# Prototipo_2.net
KiCad netlist of a schematic drawn in EAGLE
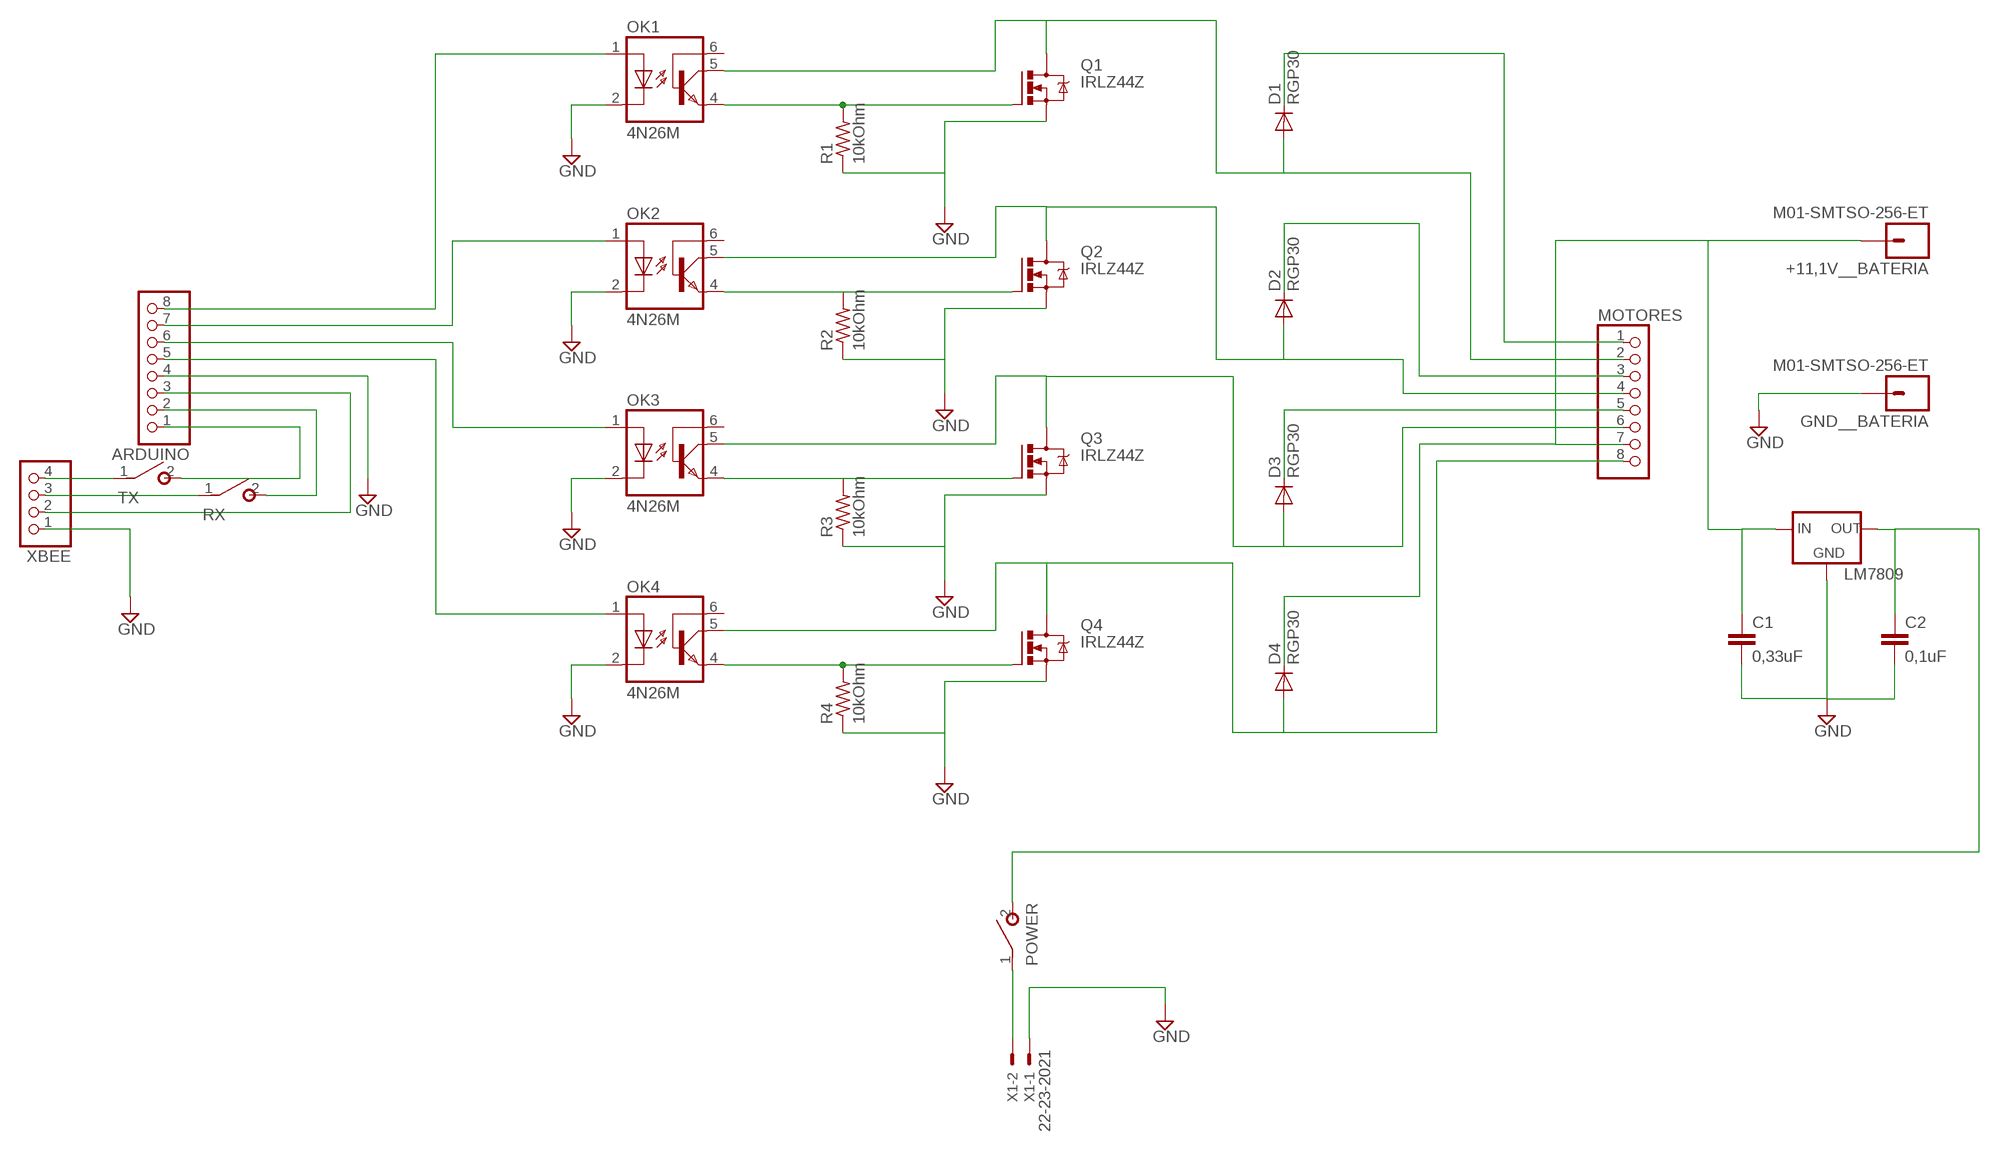
[diagram p0: schematic, sheet 1]

(export (version "E")
  (design (tool "Eeschema 10.0.6"))
  (components
    (comp (ref "+11,1V__BATERIA")
      (value "M01-SMTSO-256-ET")
      (footprint "eagle-import:SMTSO-256-ET")
      (libsource (lib "eagle-import") (part "M01-SMTSO-256-ET"))
    )
    (comp (ref "ARDUINO")
      (value "PINHD-1X8/90")
      (footprint "eagle-import:1X08_90")
      (libsource (lib "eagle-import") (part "PINHD-1X8/90"))
    )
    (comp (ref "C1")
      (value "0,33uF")
      (footprint "eagle-import:C050-030X075")
      (libsource (lib "eagle-import") (part "C-EU050-030X075"))
    )
    (comp (ref "C2")
      (value "0,1uF")
      (footprint "eagle-import:C050-030X075")
      (libsource (lib "eagle-import") (part "C-EU050-030X075"))
    )
    (comp (ref "D1")
      (value "RGP30")
      (footprint "eagle-import:DO201-15")
      (libsource (lib "eagle-import") (part "RGP30"))
    )
    (comp (ref "D2")
      (value "RGP30")
      (footprint "eagle-import:DO201-15")
      (libsource (lib "eagle-import") (part "RGP30"))
    )
    (comp (ref "D3")
      (value "RGP30")
      (footprint "eagle-import:DO201-15")
      (libsource (lib "eagle-import") (part "RGP30"))
    )
    (comp (ref "D4")
      (value "RGP30")
      (footprint "eagle-import:DO201-15")
      (libsource (lib "eagle-import") (part "RGP30"))
    )
    (comp (ref "GND__BATERIA")
      (value "M01-SMTSO-256-ET")
      (footprint "eagle-import:SMTSO-256-ET")
      (libsource (lib "eagle-import") (part "M01-SMTSO-256-ET"))
    )
    (comp (ref "LM7809")
      (value "78XXL")
      (footprint "eagle-import:78XXL")
      (libsource (lib "eagle-import") (part "78XXL"))
    )
    (comp (ref "MOTORES")
      (value "PINHD-1X8/90")
      (footprint "eagle-import:1X08_90")
      (libsource (lib "eagle-import") (part "PINHD-1X8/90"))
    )
    (comp (ref "OK1")
      (value "4N26M")
      (footprint "eagle-import:DIL06")
      (fields (field (name "MPN") "4N26-M"))
      (libsource (lib "eagle-import") (part "4N?M26"))
    )
    (comp (ref "OK2")
      (value "4N26M")
      (footprint "eagle-import:DIL06")
      (fields (field (name "MPN") "4N26-M"))
      (libsource (lib "eagle-import") (part "4N?M26"))
    )
    (comp (ref "OK3")
      (value "4N26M")
      (footprint "eagle-import:DIL06")
      (fields (field (name "MPN") "4N26-M"))
      (libsource (lib "eagle-import") (part "4N?M26"))
    )
    (comp (ref "OK4")
      (value "4N26M")
      (footprint "eagle-import:DIL06")
      (fields (field (name "MPN") "4N26-M"))
      (libsource (lib "eagle-import") (part "4N?M26"))
    )
    (comp (ref "POWER")
      (value "SPST")
      (footprint "eagle-import:SPST")
      (libsource (lib "eagle-import") (part "SPST"))
    )
    (comp (ref "Q1")
      (value "IRLZ44Z")
      (footprint "eagle-import:TO220BH")
      (libsource (lib "eagle-import") (part "IRLZ44Z"))
    )
    (comp (ref "Q2")
      (value "IRLZ44Z")
      (footprint "eagle-import:TO220BH")
      (libsource (lib "eagle-import") (part "IRLZ44Z"))
    )
    (comp (ref "Q3")
      (value "IRLZ44Z")
      (footprint "eagle-import:TO220BH")
      (libsource (lib "eagle-import") (part "IRLZ44Z"))
    )
    (comp (ref "Q4")
      (value "IRLZ44Z")
      (footprint "eagle-import:TO220BH")
      (libsource (lib "eagle-import") (part "IRLZ44Z"))
    )
    (comp (ref "R1")
      (value "10kOhm")
      (footprint "eagle-import:0207_7")
      (libsource (lib "eagle-import") (part "R-US_0207/7"))
    )
    (comp (ref "R2")
      (value "10kOhm")
      (footprint "eagle-import:0207_7")
      (libsource (lib "eagle-import") (part "R-US_0207/7"))
    )
    (comp (ref "R3")
      (value "10kOhm")
      (footprint "eagle-import:0207_7")
      (libsource (lib "eagle-import") (part "R-US_0207/7"))
    )
    (comp (ref "R4")
      (value "10kOhm")
      (footprint "eagle-import:0207_7")
      (libsource (lib "eagle-import") (part "R-US_0207/7"))
    )
    (comp (ref "RX")
      (value "SPST")
      (footprint "eagle-import:SPST")
      (libsource (lib "eagle-import") (part "SPST"))
    )
    (comp (ref "TX")
      (value "SPST")
      (footprint "eagle-import:SPST")
      (libsource (lib "eagle-import") (part "SPST"))
    )
    (comp (ref "X1")
      (value "22-23-2021")
      (footprint "eagle-import:22-23-2021")
      (fields (field (name "MF") "MOLEX"))
      (libsource (lib "eagle-import") (part "22-23-2021"))
    )
    (comp (ref "XBEE")
      (value "PINHD-1X4")
      (footprint "eagle-import:1X04")
      (libsource (lib "eagle-import") (part "PINHD-1X4"))
    )
  )
  (nets
    (net (code "1") (name "GND") (class "Default")
      (node (ref "ARDUINO") (pin "4") (pinfunction "4_4") (pintype "passive"))
      (node (ref "C1") (pin "2") (pinfunction "2_2") (pintype "passive"))
      (node (ref "C2") (pin "2") (pinfunction "2_2") (pintype "passive"))
      (node (ref "GND__BATERIA") (pin "P$1") (pinfunction "1_P$1") (pintype "passive"))
      (node (ref "LM7809") (pin "GND") (pinfunction "GND_GND") (pintype "input"))
      (node (ref "OK1") (pin "2") (pinfunction "C_2") (pintype "passive"))
      (node (ref "OK2") (pin "2") (pinfunction "C_2") (pintype "passive"))
      (node (ref "OK3") (pin "2") (pinfunction "C_2") (pintype "passive"))
      (node (ref "OK4") (pin "2") (pinfunction "C_2") (pintype "passive"))
      (node (ref "Q1") (pin "S") (pinfunction "S_S") (pintype "passive"))
      (node (ref "Q2") (pin "S") (pinfunction "S_S") (pintype "passive"))
      (node (ref "Q3") (pin "S") (pinfunction "S_S") (pintype "passive"))
      (node (ref "Q4") (pin "S") (pinfunction "S_S") (pintype "passive"))
      (node (ref "R1") (pin "1") (pinfunction "1_1") (pintype "passive"))
      (node (ref "R2") (pin "1") (pinfunction "1_1") (pintype "passive"))
      (node (ref "R3") (pin "1") (pinfunction "1_1") (pintype "passive"))
      (node (ref "R4") (pin "1") (pinfunction "1_1") (pintype "passive"))
      (node (ref "X1") (pin "1") (pinfunction "S_1") (pintype "passive"))
      (node (ref "XBEE") (pin "1") (pinfunction "1_1") (pintype "passive"))
    )
    (net (code "2") (name "Net-(+11,1V__BATERIA-1)") (class "Default")
      (node (ref "+11,1V__BATERIA") (pin "P$1") (pinfunction "1_P$1") (pintype "passive"))
      (node (ref "C1") (pin "1") (pinfunction "1_1") (pintype "passive"))
      (node (ref "D1") (pin "C") (pinfunction "C_C") (pintype "passive"))
      (node (ref "D2") (pin "C") (pinfunction "C_C") (pintype "passive"))
      (node (ref "D3") (pin "C") (pinfunction "C_C") (pintype "passive"))
      (node (ref "D4") (pin "C") (pinfunction "C_C") (pintype "passive"))
      (node (ref "LM7809") (pin "IN") (pinfunction "IN_IN") (pintype "input"))
      (node (ref "MOTORES") (pin "1") (pinfunction "1_1") (pintype "passive"))
      (node (ref "MOTORES") (pin "3") (pinfunction "3_3") (pintype "passive"))
      (node (ref "MOTORES") (pin "5") (pinfunction "5_5") (pintype "passive"))
      (node (ref "MOTORES") (pin "7") (pinfunction "7_7") (pintype "passive"))
    )
    (net (code "3") (name "Net-(ARDUINO-Pad3)") (class "Default")
      (node (ref "ARDUINO") (pin "3") (pinfunction "3_3") (pintype "passive"))
      (node (ref "XBEE") (pin "2") (pinfunction "2_2") (pintype "passive"))
    )
    (net (code "4") (name "Net-(OK1-A)") (class "Default")
      (node (ref "ARDUINO") (pin "8") (pinfunction "8_8") (pintype "passive"))
      (node (ref "OK1") (pin "1") (pinfunction "A_1") (pintype "passive"))
    )
    (net (code "5") (name "Net-(OK1-COL)") (class "Default")
      (node (ref "D1") (pin "A") (pinfunction "A_A") (pintype "passive"))
      (node (ref "MOTORES") (pin "2") (pinfunction "2_2") (pintype "passive"))
      (node (ref "OK1") (pin "5") (pinfunction "COL_5") (pintype "passive"))
      (node (ref "Q1") (pin "D") (pinfunction "D_D") (pintype "passive"))
    )
    (net (code "6") (name "Net-(OK1-EMI)") (class "Default")
      (node (ref "OK1") (pin "4") (pinfunction "EMI_4") (pintype "passive"))
      (node (ref "Q1") (pin "G") (pinfunction "G_G") (pintype "passive"))
      (node (ref "R1") (pin "2") (pinfunction "2_2") (pintype "passive"))
    )
    (net (code "7") (name "Net-(OK2-A)") (class "Default")
      (node (ref "ARDUINO") (pin "7") (pinfunction "7_7") (pintype "passive"))
      (node (ref "OK2") (pin "1") (pinfunction "A_1") (pintype "passive"))
    )
    (net (code "8") (name "Net-(OK2-COL)") (class "Default")
      (node (ref "D2") (pin "A") (pinfunction "A_A") (pintype "passive"))
      (node (ref "MOTORES") (pin "4") (pinfunction "4_4") (pintype "passive"))
      (node (ref "OK2") (pin "5") (pinfunction "COL_5") (pintype "passive"))
      (node (ref "Q2") (pin "D") (pinfunction "D_D") (pintype "passive"))
    )
    (net (code "9") (name "Net-(OK2-EMI)") (class "Default")
      (node (ref "OK2") (pin "4") (pinfunction "EMI_4") (pintype "passive"))
      (node (ref "Q2") (pin "G") (pinfunction "G_G") (pintype "passive"))
      (node (ref "R2") (pin "2") (pinfunction "2_2") (pintype "passive"))
    )
    (net (code "10") (name "Net-(OK3-A)") (class "Default")
      (node (ref "ARDUINO") (pin "6") (pinfunction "6_6") (pintype "passive"))
      (node (ref "OK3") (pin "1") (pinfunction "A_1") (pintype "passive"))
    )
    (net (code "11") (name "Net-(OK3-COL)") (class "Default")
      (node (ref "D3") (pin "A") (pinfunction "A_A") (pintype "passive"))
      (node (ref "MOTORES") (pin "6") (pinfunction "6_6") (pintype "passive"))
      (node (ref "OK3") (pin "5") (pinfunction "COL_5") (pintype "passive"))
      (node (ref "Q3") (pin "D") (pinfunction "D_D") (pintype "passive"))
    )
    (net (code "12") (name "Net-(OK3-EMI)") (class "Default")
      (node (ref "OK3") (pin "4") (pinfunction "EMI_4") (pintype "passive"))
      (node (ref "Q3") (pin "G") (pinfunction "G_G") (pintype "passive"))
      (node (ref "R3") (pin "2") (pinfunction "2_2") (pintype "passive"))
    )
    (net (code "13") (name "Net-(OK4-A)") (class "Default")
      (node (ref "ARDUINO") (pin "5") (pinfunction "5_5") (pintype "passive"))
      (node (ref "OK4") (pin "1") (pinfunction "A_1") (pintype "passive"))
    )
    (net (code "14") (name "Net-(OK4-COL)") (class "Default")
      (node (ref "D4") (pin "A") (pinfunction "A_A") (pintype "passive"))
      (node (ref "MOTORES") (pin "8") (pinfunction "8_8") (pintype "passive"))
      (node (ref "OK4") (pin "5") (pinfunction "COL_5") (pintype "passive"))
      (node (ref "Q4") (pin "D") (pinfunction "D_D") (pintype "passive"))
    )
    (net (code "15") (name "Net-(OK4-EMI)") (class "Default")
      (node (ref "OK4") (pin "4") (pinfunction "EMI_4") (pintype "passive"))
      (node (ref "Q4") (pin "G") (pinfunction "G_G") (pintype "passive"))
      (node (ref "R4") (pin "2") (pinfunction "2_2") (pintype "passive"))
    )
    (net (code "16") (name "Net-(POWER-P)") (class "Default")
      (node (ref "POWER") (pin "1") (pinfunction "P_1") (pintype "passive"))
      (node (ref "X1") (pin "2") (pinfunction "S_2") (pintype "passive"))
    )
    (net (code "17") (name "Net-(POWER-S)") (class "Default")
      (node (ref "C2") (pin "1") (pinfunction "1_1") (pintype "passive"))
      (node (ref "LM7809") (pin "OUT") (pinfunction "OUT_OUT") (pintype "passive"))
      (node (ref "POWER") (pin "2") (pinfunction "S_2") (pintype "passive"))
    )
    (net (code "18") (name "Net-(RX-P)") (class "Default")
      (node (ref "RX") (pin "1") (pinfunction "P_1") (pintype "passive"))
      (node (ref "XBEE") (pin "3") (pinfunction "3_3") (pintype "passive"))
    )
    (net (code "19") (name "Net-(RX-S)") (class "Default")
      (node (ref "ARDUINO") (pin "2") (pinfunction "2_2") (pintype "passive"))
      (node (ref "RX") (pin "2") (pinfunction "S_2") (pintype "passive"))
    )
    (net (code "20") (name "Net-(TX-P)") (class "Default")
      (node (ref "TX") (pin "1") (pinfunction "P_1") (pintype "passive"))
      (node (ref "XBEE") (pin "4") (pinfunction "4_4") (pintype "passive"))
    )
    (net (code "21") (name "Net-(TX-S)") (class "Default")
      (node (ref "ARDUINO") (pin "1") (pinfunction "1_1") (pintype "passive"))
      (node (ref "TX") (pin "2") (pinfunction "S_2") (pintype "passive"))
    )
    (net (code "22") (name "unconnected-(OK1-BAS-Pad6)") (class "Default")
      (node (ref "OK1") (pin "6") (pinfunction "BAS_6") (pintype "passive"))
    )
    (net (code "23") (name "unconnected-(OK2-BAS-Pad6)") (class "Default")
      (node (ref "OK2") (pin "6") (pinfunction "BAS_6") (pintype "passive"))
    )
    (net (code "24") (name "unconnected-(OK3-BAS-Pad6)") (class "Default")
      (node (ref "OK3") (pin "6") (pinfunction "BAS_6") (pintype "passive"))
    )
    (net (code "25") (name "unconnected-(OK4-BAS-Pad6)") (class "Default")
      (node (ref "OK4") (pin "6") (pinfunction "BAS_6") (pintype "passive"))
    )
  )
)
